# cable_1.net
KiCad netlist of a schematic drawn in EAGLE
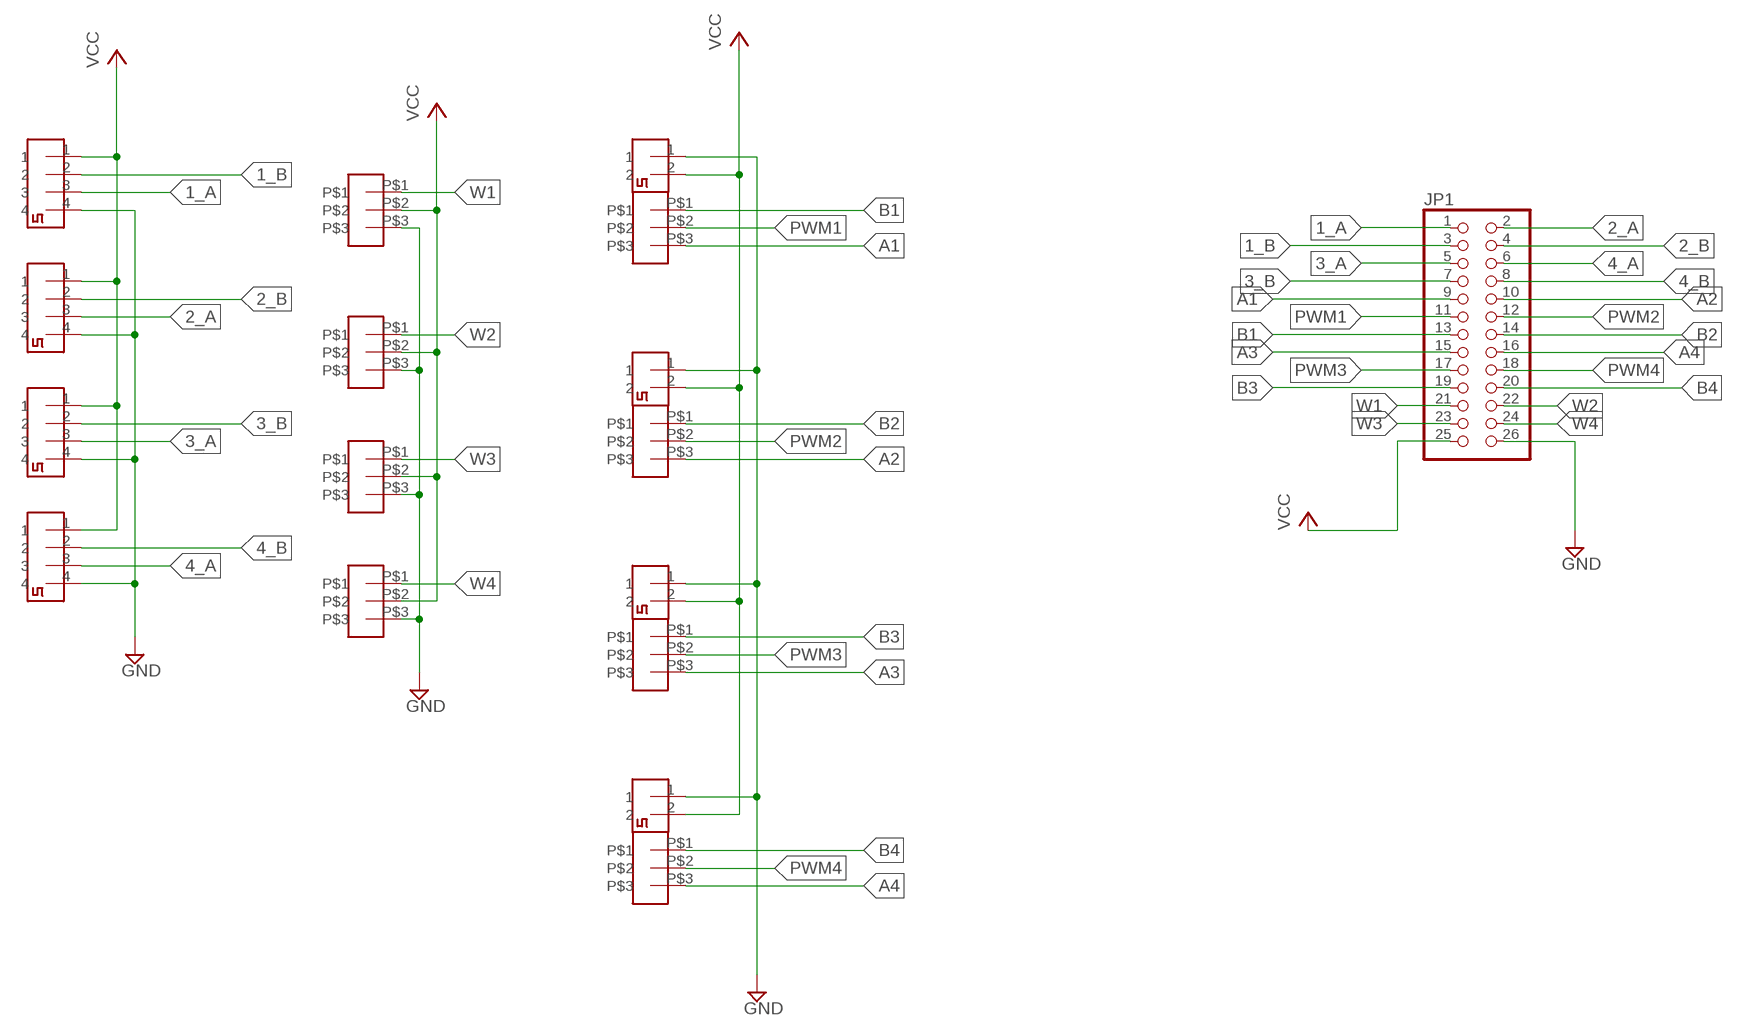
[diagram p0: schematic, sheet 1]

(export (version "E")
  (design (tool "Eeschema 10.0.6"))
  (components
    (comp (ref "3PIN1")
      (value "3PIN")
      (footprint "eagle-import:3PIN")
      (libsource (lib "eagle-import") (part "3PIN"))
    )
    (comp (ref "3PIN2")
      (value "3PIN")
      (footprint "eagle-import:3PIN")
      (libsource (lib "eagle-import") (part "3PIN"))
    )
    (comp (ref "3PIN3")
      (value "3PIN")
      (footprint "eagle-import:3PIN")
      (libsource (lib "eagle-import") (part "3PIN"))
    )
    (comp (ref "3PIN4")
      (value "3PIN")
      (footprint "eagle-import:3PIN")
      (libsource (lib "eagle-import") (part "3PIN"))
    )
    (comp (ref "3PIN5")
      (value "3PIN")
      (footprint "eagle-import:3PIN")
      (libsource (lib "eagle-import") (part "3PIN"))
    )
    (comp (ref "3PIN6")
      (value "3PIN")
      (footprint "eagle-import:3PIN")
      (libsource (lib "eagle-import") (part "3PIN"))
    )
    (comp (ref "3PIN7")
      (value "3PIN")
      (footprint "eagle-import:3PIN")
      (libsource (lib "eagle-import") (part "3PIN"))
    )
    (comp (ref "3PIN8")
      (value "3PIN")
      (footprint "eagle-import:3PIN")
      (libsource (lib "eagle-import") (part "3PIN"))
    )
    (comp (ref "CONNECTOR1")
      (value "2PIN")
      (footprint "eagle-import:2PIN")
      (libsource (lib "eagle-import") (part "2PIN"))
    )
    (comp (ref "CONNECTOR2")
      (value "2PIN")
      (footprint "eagle-import:2PIN")
      (libsource (lib "eagle-import") (part "2PIN"))
    )
    (comp (ref "CONNECTOR3")
      (value "2PIN")
      (footprint "eagle-import:2PIN")
      (libsource (lib "eagle-import") (part "2PIN"))
    )
    (comp (ref "CONNECTOR4")
      (value "2PIN")
      (footprint "eagle-import:2PIN")
      (libsource (lib "eagle-import") (part "2PIN"))
    )
    (comp (ref "CONNECTOR5")
      (value "2PIN")
      (footprint "eagle-import:2PIN")
      (libsource (lib "eagle-import") (part "4pin_small_2PIN"))
    )
    (comp (ref "CONNECTOR6")
      (value "2PIN")
      (footprint "eagle-import:2PIN")
      (libsource (lib "eagle-import") (part "4pin_small_2PIN"))
    )
    (comp (ref "CONNECTOR7")
      (value "2PIN")
      (footprint "eagle-import:2PIN")
      (libsource (lib "eagle-import") (part "4pin_small_2PIN"))
    )
    (comp (ref "CONNECTOR8")
      (value "2PIN")
      (footprint "eagle-import:2PIN")
      (libsource (lib "eagle-import") (part "4pin_small_2PIN"))
    )
    (comp (ref "JP1")
      (value "PINHD-2X13")
      (footprint "eagle-import:2X13")
      (libsource (lib "eagle-import") (part "PINHD-2X13"))
    )
  )
  (nets
    (net (code "1") (name "1_A") (class "Default")
      (node (ref "CONNECTOR5") (pin "3") (pinfunction "3_3") (pintype "bidirectional"))
      (node (ref "JP1") (pin "1") (pinfunction "1_1") (pintype "passive"))
    )
    (net (code "2") (name "1_B") (class "Default")
      (node (ref "CONNECTOR5") (pin "2") (pinfunction "2_2") (pintype "bidirectional"))
      (node (ref "JP1") (pin "3") (pinfunction "3_3") (pintype "passive"))
    )
    (net (code "3") (name "2_A") (class "Default")
      (node (ref "CONNECTOR6") (pin "3") (pinfunction "3_3") (pintype "bidirectional"))
      (node (ref "JP1") (pin "2") (pinfunction "2_2") (pintype "passive"))
    )
    (net (code "4") (name "2_B") (class "Default")
      (node (ref "CONNECTOR6") (pin "2") (pinfunction "2_2") (pintype "bidirectional"))
      (node (ref "JP1") (pin "4") (pinfunction "4_4") (pintype "passive"))
    )
    (net (code "5") (name "3_A") (class "Default")
      (node (ref "CONNECTOR7") (pin "3") (pinfunction "3_3") (pintype "bidirectional"))
      (node (ref "JP1") (pin "5") (pinfunction "5_5") (pintype "passive"))
    )
    (net (code "6") (name "3_B") (class "Default")
      (node (ref "CONNECTOR7") (pin "2") (pinfunction "2_2") (pintype "bidirectional"))
      (node (ref "JP1") (pin "7") (pinfunction "7_7") (pintype "passive"))
    )
    (net (code "7") (name "4_A") (class "Default")
      (node (ref "CONNECTOR8") (pin "3") (pinfunction "3_3") (pintype "bidirectional"))
      (node (ref "JP1") (pin "6") (pinfunction "6_6") (pintype "passive"))
    )
    (net (code "8") (name "4_B") (class "Default")
      (node (ref "CONNECTOR8") (pin "2") (pinfunction "2_2") (pintype "bidirectional"))
      (node (ref "JP1") (pin "8") (pinfunction "8_8") (pintype "passive"))
    )
    (net (code "9") (name "A1") (class "Default")
      (node (ref "3PIN5") (pin "P$3") (pinfunction "P$3_P$3") (pintype "bidirectional"))
      (node (ref "JP1") (pin "9") (pinfunction "9_9") (pintype "passive"))
    )
    (net (code "10") (name "A2") (class "Default")
      (node (ref "3PIN6") (pin "P$3") (pinfunction "P$3_P$3") (pintype "bidirectional"))
      (node (ref "JP1") (pin "10") (pinfunction "10_10") (pintype "passive"))
    )
    (net (code "11") (name "A3") (class "Default")
      (node (ref "3PIN7") (pin "P$3") (pinfunction "P$3_P$3") (pintype "bidirectional"))
      (node (ref "JP1") (pin "15") (pinfunction "15_15") (pintype "passive"))
    )
    (net (code "12") (name "A4") (class "Default")
      (node (ref "3PIN8") (pin "P$3") (pinfunction "P$3_P$3") (pintype "bidirectional"))
      (node (ref "JP1") (pin "16") (pinfunction "16_16") (pintype "passive"))
    )
    (net (code "13") (name "B1") (class "Default")
      (node (ref "3PIN5") (pin "P$1") (pinfunction "P$1_P$1") (pintype "bidirectional"))
      (node (ref "JP1") (pin "13") (pinfunction "13_13") (pintype "passive"))
    )
    (net (code "14") (name "B2") (class "Default")
      (node (ref "3PIN6") (pin "P$1") (pinfunction "P$1_P$1") (pintype "bidirectional"))
      (node (ref "JP1") (pin "14") (pinfunction "14_14") (pintype "passive"))
    )
    (net (code "15") (name "B3") (class "Default")
      (node (ref "3PIN7") (pin "P$1") (pinfunction "P$1_P$1") (pintype "bidirectional"))
      (node (ref "JP1") (pin "19") (pinfunction "19_19") (pintype "passive"))
    )
    (net (code "16") (name "B4") (class "Default")
      (node (ref "3PIN8") (pin "P$1") (pinfunction "P$1_P$1") (pintype "bidirectional"))
      (node (ref "JP1") (pin "20") (pinfunction "20_20") (pintype "passive"))
    )
    (net (code "17") (name "GND") (class "Default")
      (node (ref "3PIN1") (pin "P$3") (pinfunction "P$3_P$3") (pintype "bidirectional"))
      (node (ref "3PIN2") (pin "P$3") (pinfunction "P$3_P$3") (pintype "bidirectional"))
      (node (ref "3PIN3") (pin "P$3") (pinfunction "P$3_P$3") (pintype "bidirectional"))
      (node (ref "3PIN4") (pin "P$3") (pinfunction "P$3_P$3") (pintype "bidirectional"))
      (node (ref "CONNECTOR1") (pin "1") (pinfunction "1_1") (pintype "bidirectional"))
      (node (ref "CONNECTOR2") (pin "1") (pinfunction "1_1") (pintype "bidirectional"))
      (node (ref "CONNECTOR3") (pin "1") (pinfunction "1_1") (pintype "bidirectional"))
      (node (ref "CONNECTOR4") (pin "1") (pinfunction "1_1") (pintype "bidirectional"))
      (node (ref "CONNECTOR5") (pin "4") (pinfunction "4_4") (pintype "bidirectional"))
      (node (ref "CONNECTOR6") (pin "4") (pinfunction "4_4") (pintype "bidirectional"))
      (node (ref "CONNECTOR7") (pin "4") (pinfunction "4_4") (pintype "bidirectional"))
      (node (ref "CONNECTOR8") (pin "4") (pinfunction "4_4") (pintype "bidirectional"))
      (node (ref "JP1") (pin "26") (pinfunction "26_26") (pintype "passive"))
    )
    (net (code "18") (name "PWM1") (class "Default")
      (node (ref "3PIN5") (pin "P$2") (pinfunction "P$2_P$2") (pintype "bidirectional"))
      (node (ref "JP1") (pin "11") (pinfunction "11_11") (pintype "passive"))
    )
    (net (code "19") (name "PWM2") (class "Default")
      (node (ref "3PIN6") (pin "P$2") (pinfunction "P$2_P$2") (pintype "bidirectional"))
      (node (ref "JP1") (pin "12") (pinfunction "12_12") (pintype "passive"))
    )
    (net (code "20") (name "PWM3") (class "Default")
      (node (ref "3PIN7") (pin "P$2") (pinfunction "P$2_P$2") (pintype "bidirectional"))
      (node (ref "JP1") (pin "17") (pinfunction "17_17") (pintype "passive"))
    )
    (net (code "21") (name "PWM4") (class "Default")
      (node (ref "3PIN8") (pin "P$2") (pinfunction "P$2_P$2") (pintype "bidirectional"))
      (node (ref "JP1") (pin "18") (pinfunction "18_18") (pintype "passive"))
    )
    (net (code "22") (name "VCC") (class "Default")
      (node (ref "3PIN1") (pin "P$2") (pinfunction "P$2_P$2") (pintype "bidirectional"))
      (node (ref "3PIN2") (pin "P$2") (pinfunction "P$2_P$2") (pintype "bidirectional"))
      (node (ref "3PIN3") (pin "P$2") (pinfunction "P$2_P$2") (pintype "bidirectional"))
      (node (ref "3PIN4") (pin "P$2") (pinfunction "P$2_P$2") (pintype "bidirectional"))
      (node (ref "CONNECTOR1") (pin "2") (pinfunction "2_2") (pintype "bidirectional"))
      (node (ref "CONNECTOR2") (pin "2") (pinfunction "2_2") (pintype "bidirectional"))
      (node (ref "CONNECTOR3") (pin "2") (pinfunction "2_2") (pintype "bidirectional"))
      (node (ref "CONNECTOR4") (pin "2") (pinfunction "2_2") (pintype "bidirectional"))
      (node (ref "CONNECTOR5") (pin "1") (pinfunction "1_1") (pintype "bidirectional"))
      (node (ref "CONNECTOR6") (pin "1") (pinfunction "1_1") (pintype "bidirectional"))
      (node (ref "CONNECTOR7") (pin "1") (pinfunction "1_1") (pintype "bidirectional"))
      (node (ref "CONNECTOR8") (pin "1") (pinfunction "1_1") (pintype "bidirectional"))
      (node (ref "JP1") (pin "25") (pinfunction "25_25") (pintype "passive"))
    )
    (net (code "23") (name "W1") (class "Default")
      (node (ref "3PIN1") (pin "P$1") (pinfunction "P$1_P$1") (pintype "bidirectional"))
      (node (ref "JP1") (pin "21") (pinfunction "21_21") (pintype "passive"))
    )
    (net (code "24") (name "W2") (class "Default")
      (node (ref "3PIN2") (pin "P$1") (pinfunction "P$1_P$1") (pintype "bidirectional"))
      (node (ref "JP1") (pin "22") (pinfunction "22_22") (pintype "passive"))
    )
    (net (code "25") (name "W3") (class "Default")
      (node (ref "3PIN3") (pin "P$1") (pinfunction "P$1_P$1") (pintype "bidirectional"))
      (node (ref "JP1") (pin "23") (pinfunction "23_23") (pintype "passive"))
    )
    (net (code "26") (name "W4") (class "Default")
      (node (ref "3PIN4") (pin "P$1") (pinfunction "P$1_P$1") (pintype "bidirectional"))
      (node (ref "JP1") (pin "24") (pinfunction "24_24") (pintype "passive"))
    )
  )
)
